# MIRA220CSP-Sheet1.net
KiCad netlist of a schematic drawn in Altium Designer
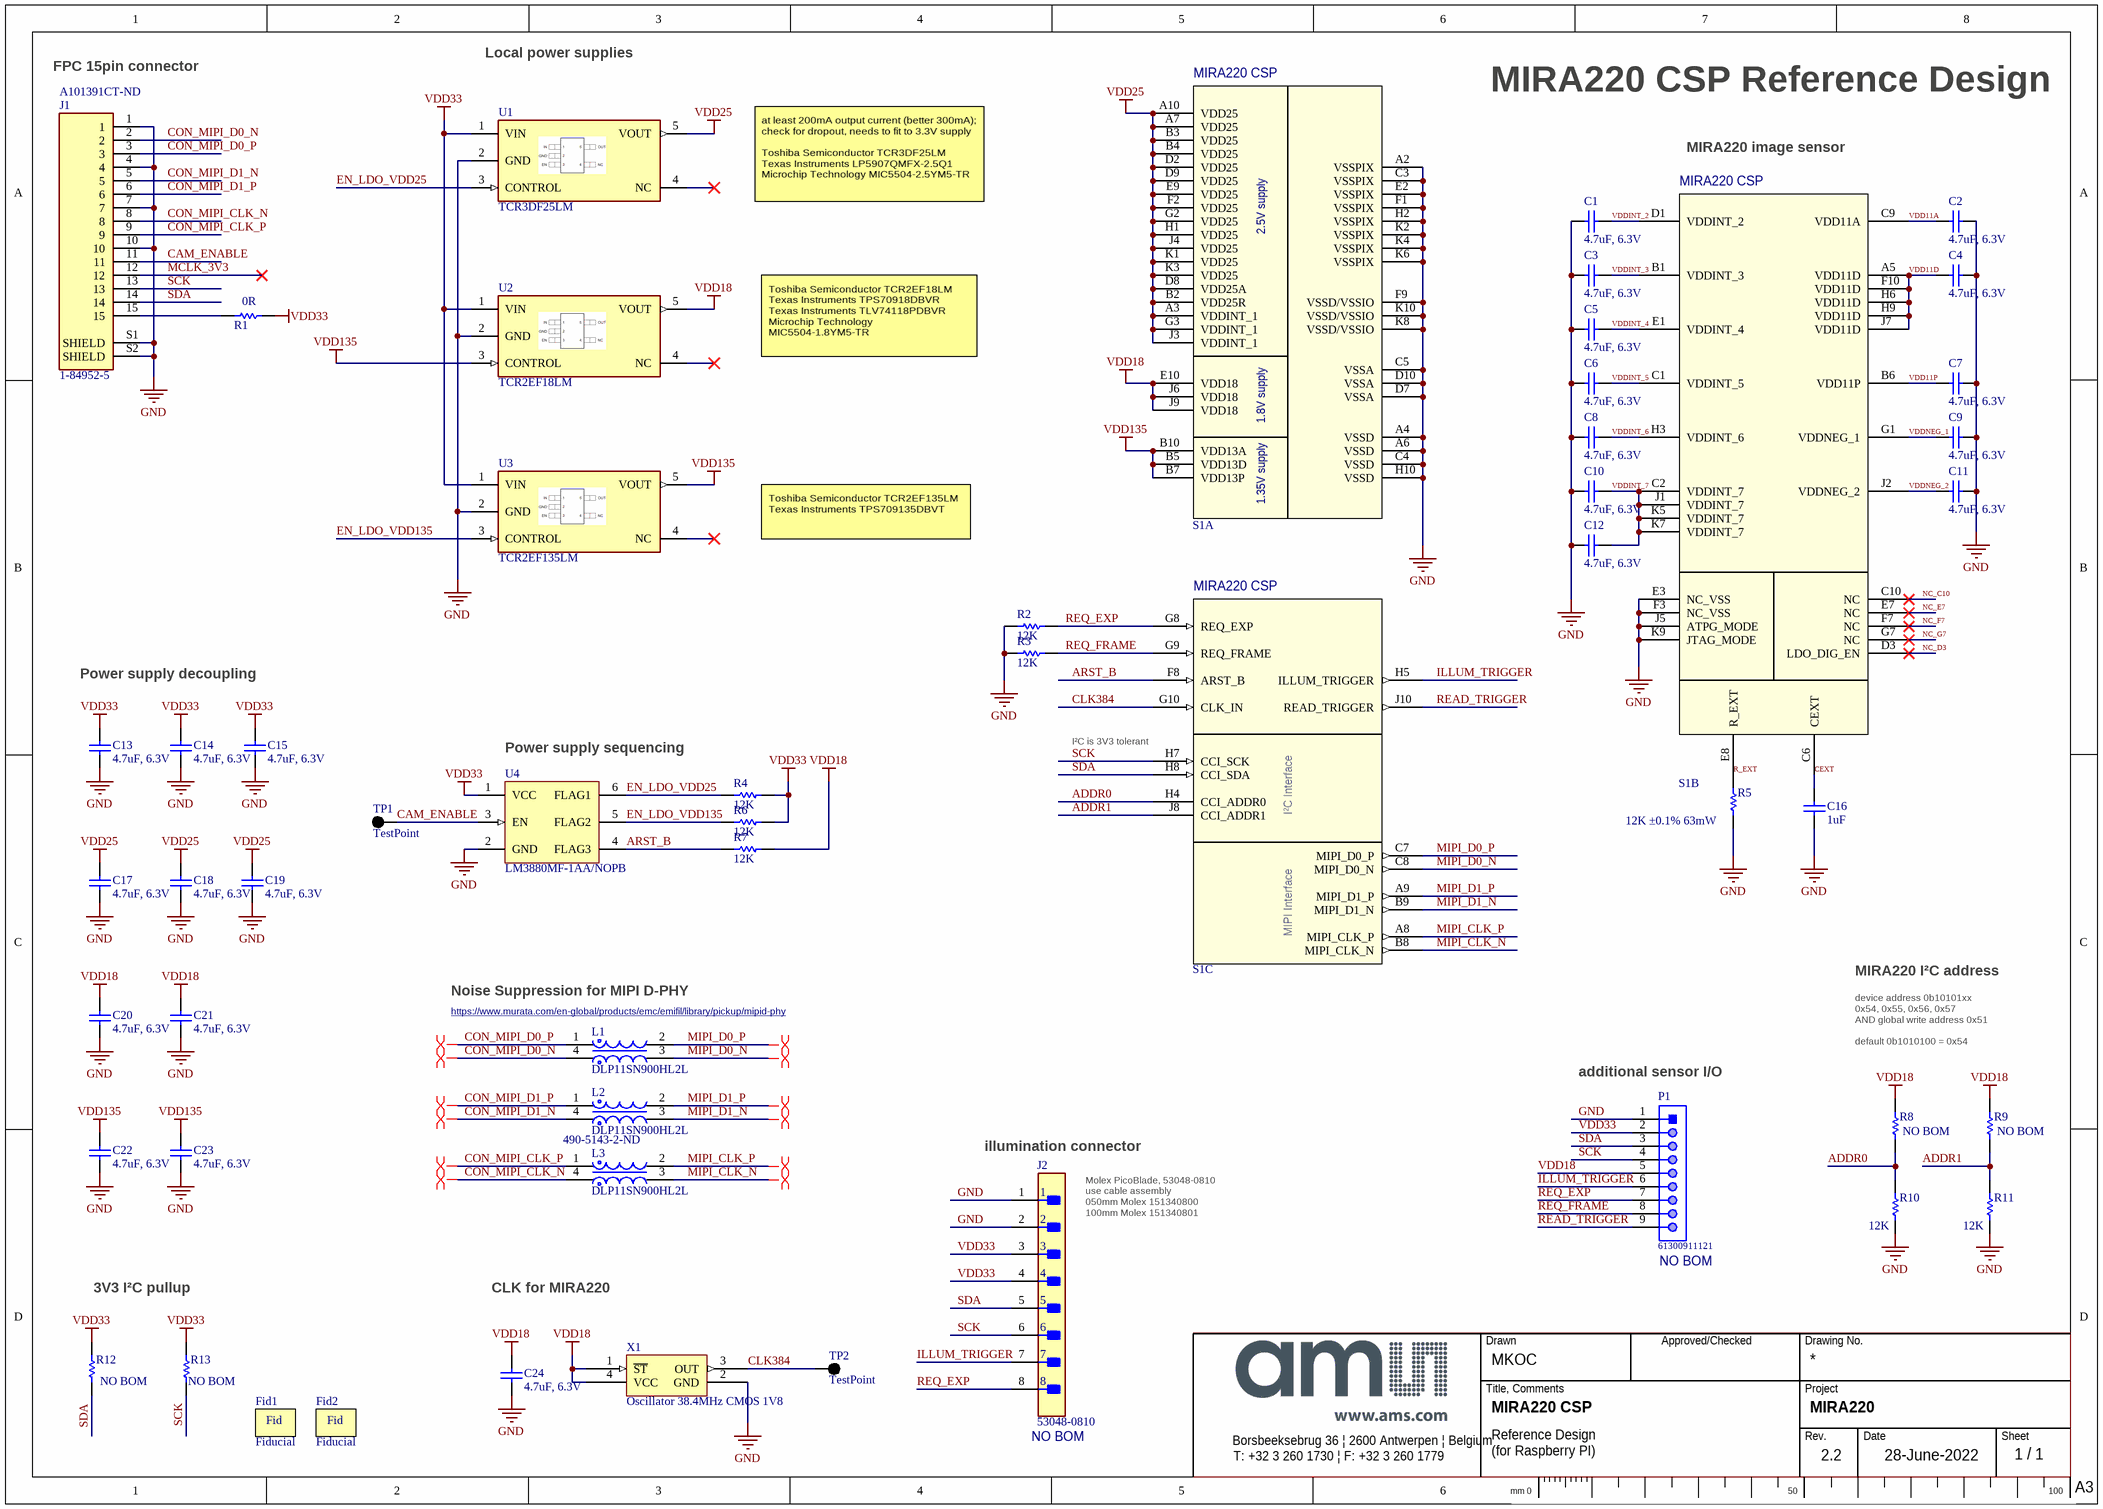
[diagram p0: MIRA220CSP-Sheet1.SchDoc]

(export (version "E")
  (design (tool "Eeschema 10.0.6"))
  (components
    (comp (ref "C1")
      (value "4.7uF, 6.3V")
      (footprint "MIRA220CSP:CAPC0402_N")
      (description "GRM155R60J475ME47D Capacitor 4.7uF, 6.3V, X5R, 0402, ±10% Tolerance,")
      (fields (field (name "TOLERANCE") "±10%") (field (name "PART NUMBER") "GRM155R60J475ME47D"))
      (libsource (lib "altiumlib") (part "cap_unpolarised"))
    )
    (comp (ref "C2")
      (value "4.7uF, 6.3V")
      (footprint "MIRA220CSP:CAPC0402_N")
      (description "GRM155R60J475ME47D Capacitor 4.7uF, 6.3V, X5R, 0402, ±10% Tolerance,")
      (fields (field (name "TOLERANCE") "±10%") (field (name "PART NUMBER") "GRM155R60J475ME47D"))
      (libsource (lib "altiumlib") (part "cap_unpolarised"))
    )
    (comp (ref "C3")
      (value "4.7uF, 6.3V")
      (footprint "MIRA220CSP:CAPC0402_N")
      (description "GRM155R60J475ME47D Capacitor 4.7uF, 6.3V, X5R, 0402, ±10% Tolerance,")
      (fields (field (name "TOLERANCE") "±10%") (field (name "PART NUMBER") "GRM155R60J475ME47D"))
      (libsource (lib "altiumlib") (part "cap_unpolarised"))
    )
    (comp (ref "C4")
      (value "4.7uF, 6.3V")
      (footprint "MIRA220CSP:CAPC0402_N")
      (description "GRM155R60J475ME47D Capacitor 4.7uF, 6.3V, X5R, 0402, ±10% Tolerance,")
      (fields (field (name "TOLERANCE") "±10%") (field (name "PART NUMBER") "GRM155R60J475ME47D"))
      (libsource (lib "altiumlib") (part "cap_unpolarised"))
    )
    (comp (ref "C5")
      (value "4.7uF, 6.3V")
      (footprint "MIRA220CSP:CAPC0402_N")
      (description "GRM155R60J475ME47D Capacitor 4.7uF, 6.3V, X5R, 0402, ±10% Tolerance,")
      (fields (field (name "TOLERANCE") "±10%") (field (name "PART NUMBER") "GRM155R60J475ME47D"))
      (libsource (lib "altiumlib") (part "cap_unpolarised"))
    )
    (comp (ref "C6")
      (value "4.7uF, 6.3V")
      (footprint "MIRA220CSP:CAPC0402_N")
      (description "GRM155R60J475ME47D Capacitor 4.7uF, 6.3V, X5R, 0402, ±10% Tolerance,")
      (fields (field (name "TOLERANCE") "±10%") (field (name "PART NUMBER") "GRM155R60J475ME47D"))
      (libsource (lib "altiumlib") (part "cap_unpolarised"))
    )
    (comp (ref "C7")
      (value "4.7uF, 6.3V")
      (footprint "MIRA220CSP:CAPC0402_N")
      (description "GRM155R60J475ME47D Capacitor 4.7uF, 6.3V, X5R, 0402, ±10% Tolerance,")
      (fields (field (name "TOLERANCE") "±10%") (field (name "PART NUMBER") "GRM155R60J475ME47D"))
      (libsource (lib "altiumlib") (part "cap_unpolarised"))
    )
    (comp (ref "C8")
      (value "4.7uF, 6.3V")
      (footprint "MIRA220CSP:CAPC0402_N")
      (description "GRM155R60J475ME47D Capacitor 4.7uF, 6.3V, X5R, 0402, ±10% Tolerance,")
      (fields (field (name "TOLERANCE") "±10%") (field (name "PART NUMBER") "GRM155R60J475ME47D"))
      (libsource (lib "altiumlib") (part "cap_unpolarised"))
    )
    (comp (ref "C9")
      (value "4.7uF, 6.3V")
      (footprint "MIRA220CSP:CAPC0402_N")
      (description "GRM155R60J475ME47D Capacitor 4.7uF, 6.3V, X5R, 0402, ±10% Tolerance,")
      (fields (field (name "TOLERANCE") "±10%") (field (name "PART NUMBER") "GRM155R60J475ME47D"))
      (libsource (lib "altiumlib") (part "cap_unpolarised"))
    )
    (comp (ref "C10")
      (value "4.7uF, 6.3V")
      (footprint "MIRA220CSP:CAPC0402_N")
      (description "GRM155R60J475ME47D Capacitor 4.7uF, 6.3V, X5R, 0402, ±10% Tolerance,")
      (fields (field (name "TOLERANCE") "±10%") (field (name "PART NUMBER") "GRM155R60J475ME47D"))
      (libsource (lib "altiumlib") (part "cap_unpolarised"))
    )
    (comp (ref "C11")
      (value "4.7uF, 6.3V")
      (footprint "MIRA220CSP:CAPC0402_N")
      (description "GRM155R60J475ME47D Capacitor 4.7uF, 6.3V, X5R, 0402, ±10% Tolerance,")
      (fields (field (name "TOLERANCE") "±10%") (field (name "PART NUMBER") "GRM155R60J475ME47D"))
      (libsource (lib "altiumlib") (part "cap_unpolarised"))
    )
    (comp (ref "C12")
      (value "4.7uF, 6.3V")
      (footprint "MIRA220CSP:CAPC0402_N")
      (description "GRM155R60J475ME47D Capacitor 4.7uF, 6.3V, X5R, 0402, ±10% Tolerance,")
      (fields (field (name "TOLERANCE") "±10%") (field (name "PART NUMBER") "GRM155R60J475ME47D"))
      (libsource (lib "altiumlib") (part "cap_unpolarised"))
    )
    (comp (ref "C13")
      (value "4.7uF, 6.3V")
      (footprint "MIRA220CSP:CAPC0402_N")
      (description "GRM155R60J475ME47D Capacitor 4.7uF, 6.3V, X5R, 0402, ±10% Tolerance,")
      (fields (field (name "TOLERANCE") "±10%") (field (name "PART NUMBER") "GRM155R60J475ME47D"))
      (libsource (lib "altiumlib") (part "cap_unpolarised"))
    )
    (comp (ref "C14")
      (value "4.7uF, 6.3V")
      (footprint "MIRA220CSP:CAPC0402_N")
      (description "GRM155R60J475ME47D Capacitor 4.7uF, 6.3V, X5R, 0402, ±10% Tolerance,")
      (fields (field (name "TOLERANCE") "±10%") (field (name "PART NUMBER") "GRM155R60J475ME47D"))
      (libsource (lib "altiumlib") (part "cap_unpolarised"))
    )
    (comp (ref "C15")
      (value "4.7uF, 6.3V")
      (footprint "MIRA220CSP:CAPC0402_N")
      (description "GRM155R60J475ME47D Capacitor 4.7uF, 6.3V, X5R, 0402, ±10% Tolerance,")
      (fields (field (name "TOLERANCE") "±10%") (field (name "PART NUMBER") "GRM155R60J475ME47D"))
      (libsource (lib "altiumlib") (part "cap_unpolarised"))
    )
    (comp (ref "C16")
      (value "1uF")
      (footprint "MIRA220CSP:CAPC0402_N")
      (description "GRM155R70J105KA12J, Capacitor  0402, ±10% Tolerance, 10V, 1uF")
      (fields (field (name "PART NUMBER") "GRM155R70J105KA12J") (field (name "MANUFACTURER") "Murata"))
      (libsource (lib "altiumlib") (part "cap_unpolarised"))
    )
    (comp (ref "C17")
      (value "4.7uF, 6.3V")
      (footprint "MIRA220CSP:CAPC0402_N")
      (description "GRM155R60J475ME47D Capacitor 4.7uF, 6.3V, X5R, 0402, ±10% Tolerance,")
      (fields (field (name "TOLERANCE") "±10%") (field (name "PART NUMBER") "GRM155R60J475ME47D"))
      (libsource (lib "altiumlib") (part "cap_unpolarised"))
    )
    (comp (ref "C18")
      (value "4.7uF, 6.3V")
      (footprint "MIRA220CSP:CAPC0402_N")
      (description "GRM155R60J475ME47D Capacitor 4.7uF, 6.3V, X5R, 0402, ±10% Tolerance,")
      (fields (field (name "TOLERANCE") "±10%") (field (name "PART NUMBER") "GRM155R60J475ME47D"))
      (libsource (lib "altiumlib") (part "cap_unpolarised"))
    )
    (comp (ref "C19")
      (value "4.7uF, 6.3V")
      (footprint "MIRA220CSP:CAPC0402_N")
      (description "GRM155R60J475ME47D Capacitor 4.7uF, 6.3V, X5R, 0402, ±10% Tolerance,")
      (fields (field (name "TOLERANCE") "±10%") (field (name "PART NUMBER") "GRM155R60J475ME47D"))
      (libsource (lib "altiumlib") (part "cap_unpolarised"))
    )
    (comp (ref "C20")
      (value "4.7uF, 6.3V")
      (footprint "MIRA220CSP:CAPC0402_N")
      (description "GRM155R60J475ME47D Capacitor 4.7uF, 6.3V, X5R, 0402, ±10% Tolerance,")
      (fields (field (name "TOLERANCE") "±10%") (field (name "PART NUMBER") "GRM155R60J475ME47D"))
      (libsource (lib "altiumlib") (part "cap_unpolarised"))
    )
    (comp (ref "C21")
      (value "4.7uF, 6.3V")
      (footprint "MIRA220CSP:CAPC0402_N")
      (description "GRM155R60J475ME47D Capacitor 4.7uF, 6.3V, X5R, 0402, ±10% Tolerance,")
      (fields (field (name "TOLERANCE") "±10%") (field (name "PART NUMBER") "GRM155R60J475ME47D"))
      (libsource (lib "altiumlib") (part "cap_unpolarised"))
    )
    (comp (ref "C22")
      (value "4.7uF, 6.3V")
      (footprint "MIRA220CSP:CAPC0402_N")
      (description "GRM155R60J475ME47D Capacitor 4.7uF, 6.3V, X5R, 0402, ±10% Tolerance,")
      (fields (field (name "TOLERANCE") "±10%") (field (name "PART NUMBER") "GRM155R60J475ME47D"))
      (libsource (lib "altiumlib") (part "cap_unpolarised"))
    )
    (comp (ref "C23")
      (value "4.7uF, 6.3V")
      (footprint "MIRA220CSP:CAPC0402_N")
      (description "GRM155R60J475ME47D Capacitor 4.7uF, 6.3V, X5R, 0402, ±10% Tolerance,")
      (fields (field (name "TOLERANCE") "±10%") (field (name "PART NUMBER") "GRM155R60J475ME47D"))
      (libsource (lib "altiumlib") (part "cap_unpolarised"))
    )
    (comp (ref "C24")
      (value "4.7uF, 6.3V")
      (footprint "MIRA220CSP:CAPC0402_N")
      (description "GRM155R60J475ME47D Capacitor 4.7uF, 6.3V, X5R, 0402, ±10% Tolerance,")
      (fields (field (name "TOLERANCE") "±10%") (field (name "PART NUMBER") "GRM155R60J475ME47D"))
      (libsource (lib "altiumlib") (part "cap_unpolarised"))
    )
    (comp (ref "Fid1")
      (value "Fiducial")
      (footprint "Fiducial")
      (description "Alignment feature for PCB Assembly")
      (fields (field (name "PART NUMBER") "NA"))
      (libsource (lib "altiumlib") (part "Fiducial"))
    )
    (comp (ref "Fid2")
      (value "Fiducial")
      (footprint "Fiducial")
      (description "Alignment feature for PCB Assembly")
      (fields (field (name "PART NUMBER") "NA"))
      (libsource (lib "altiumlib") (part "Fiducial"))
    )
    (comp (ref "J1")
      (value "1-84952-5")
      (footprint "TE_1-84952-5")
      (description "Conn FPC Connector SKT 15 POS 1mm Solder RA SMD T/R")
      (fields (field (name "MF") "TE Connectivity") (field (name "SUPPLIER PART NUMBER 1") "A101391CT-ND"))
      (libsource (lib "MIRA220CSP") (part "1-84952-5"))
    )
    (comp (ref "J2")
      (value "53048-0810")
      (footprint "FP-53048-0810-MFG")
      (description "CONN HEADER R/A 8POS 1.25MM")
      (fields
        (field (name "OCTOPART") "https://octopart.com/53048-0810-molex-276821")
        (field (name "MANUFACTURER") "Molex")
      )
      (libsource (lib "Altium Content Vault") (part "99ec2b232beb5d2356d4d77f6a047f0"))
    )
    (comp (ref "L1")
      (value "DLP11SN900HL2L")
      (footprint "FP-DLP11S-MFG")
      (description "Common Mode Choke, 0504, 90Ω @ 100MHz, 1.88Ω, 20%, 150mA")
      (fields (field (name "TOLERANCE") "20%"))
      (libsource (lib "MIRA220CSP") (part "CMP-2000-06161-2"))
    )
    (comp (ref "L2")
      (value "DLP11SN900HL2L")
      (footprint "FP-DLP11S-MFG")
      (description "Common Mode Choke, 0504, 90Ω @ 100MHz, 1.88Ω, 20%, 150mA")
      (fields (field (name "TOLERANCE") "20%"))
      (libsource (lib "MIRA220CSP") (part "CMP-2000-06161-2"))
    )
    (comp (ref "L3")
      (value "DLP11SN900HL2L")
      (footprint "FP-DLP11S-MFG")
      (description "Common Mode Choke, 0504, 90Ω @ 100MHz, 1.88Ω, 20%, 150mA")
      (fields (field (name "TOLERANCE") "20%") (field (name "SUPPLIER PART NUMBER 1") "490-5143-2-ND"))
      (libsource (lib "MIRA220CSP") (part "CMP-2000-06161-2"))
    )
    (comp (ref "P1")
      (value "61300911121")
      (footprint "61300911121")
      (description "THT Vertical Pin Header WR-PHD, Pitch 2.54 mm, Single Row, 9 pins")
      (fields (field (name "MANUFACTURER") "Wurth Elektronik") (field (name "PUBLISHER") "WurthElektronik"))
      (libsource (lib "Altium Content Vault") (part "WE-CN-1P-M-R9"))
    )
    (comp (ref "R1")
      (value "0R")
      (footprint "MIRA220CSP:RESC0805_N")
      (description "Resistor 0R 0805")
      (fields (field (name "TOLERANCE") "±1%") (field (name "PART NUMBER") "MCWR08X0000FTL"))
      (libsource (lib "altiumlib") (part "Res"))
    )
    (comp (ref "R2")
      (value "12K")
      (footprint "MIRA220CSP:RESC0402_N")
      (description "Resistor 12K 0402, ±0.1% Tolerance, 63mW max Pd, 50V")
      (fields (field (name "TOLERANCE") "±0.1%") (field (name "PART NUMBER") "ERA2AEB123X"))
      (libsource (lib "altiumlib") (part "Res"))
    )
    (comp (ref "R3")
      (value "12K")
      (footprint "MIRA220CSP:RESC0402_N")
      (description "Resistor 12K 0402, ±0.1% Tolerance, 63mW max Pd, 50V")
      (fields (field (name "TOLERANCE") "±0.1%") (field (name "PART NUMBER") "ERA2AEB123X"))
      (libsource (lib "altiumlib") (part "Res"))
    )
    (comp (ref "R4")
      (value "12K")
      (footprint "MIRA220CSP:RESC0402_N")
      (description "Resistor 12K 0402, ±0.1% Tolerance, 63mW max Pd, 50V")
      (fields (field (name "TOLERANCE") "±0.1%") (field (name "PART NUMBER") "ERA2AEB123X"))
      (libsource (lib "altiumlib") (part "Res"))
    )
    (comp (ref "R5")
      (value "12K ±0.1% 63mW")
      (footprint "MIRA220CSP:RESC0402_N")
      (description "Resistor 12K 0402, ±0.1% Tolerance, 63mW max Pd, 50V")
      (fields (field (name "TOLERANCE") "±0.1%") (field (name "PART NUMBER") "ERA2AEB123X"))
      (libsource (lib "altiumlib") (part "Res"))
    )
    (comp (ref "R6")
      (value "12K")
      (footprint "MIRA220CSP:RESC0402_N")
      (description "Resistor 12K 0402, ±0.1% Tolerance, 63mW max Pd, 50V")
      (fields (field (name "TOLERANCE") "±0.1%") (field (name "PART NUMBER") "ERA2AEB123X"))
      (libsource (lib "altiumlib") (part "Res"))
    )
    (comp (ref "R7")
      (value "12K")
      (footprint "MIRA220CSP:RESC0402_N")
      (description "Resistor 12K 0402, ±0.1% Tolerance, 63mW max Pd, 50V")
      (fields (field (name "TOLERANCE") "±0.1%") (field (name "PART NUMBER") "ERA2AEB123X"))
      (libsource (lib "altiumlib") (part "Res"))
    )
    (comp (ref "R8")
      (value "NO BOM")
      (footprint "MIRA220CSP:RESC0402_N")
      (description "Resistor 12K 0402, ±0.1% Tolerance, 63mW max Pd, 50V")
      (fields (field (name "TOLERANCE") "±0.1%") (field (name "PART NUMBER") "ERA2AEB123X"))
      (libsource (lib "altiumlib") (part "Res"))
    )
    (comp (ref "R9")
      (value "NO BOM")
      (footprint "MIRA220CSP:RESC0402_N")
      (description "Resistor 12K 0402, ±0.1% Tolerance, 63mW max Pd, 50V")
      (fields (field (name "TOLERANCE") "±0.1%") (field (name "PART NUMBER") "ERA2AEB123X"))
      (libsource (lib "altiumlib") (part "Res"))
    )
    (comp (ref "R10")
      (value "12K")
      (footprint "MIRA220CSP:RESC0402_N")
      (description "Resistor 12K 0402, ±0.1% Tolerance, 63mW max Pd, 50V")
      (fields (field (name "TOLERANCE") "±0.1%") (field (name "PART NUMBER") "ERA2AEB123X"))
      (libsource (lib "altiumlib") (part "Res"))
    )
    (comp (ref "R11")
      (value "12K")
      (footprint "MIRA220CSP:RESC0402_N")
      (description "Resistor 12K 0402, ±0.1% Tolerance, 63mW max Pd, 50V")
      (fields (field (name "TOLERANCE") "±0.1%") (field (name "PART NUMBER") "ERA2AEB123X"))
      (libsource (lib "altiumlib") (part "Res"))
    )
    (comp (ref "R12")
      (value "NO BOM")
      (footprint "MIRA220CSP:RESC0402_N")
      (description "Resistor 2K 0402, ±0.1% Tolerance, 63mW max Pd, 50V")
      (fields (field (name "TOLERANCE") "±0.1%") (field (name "PART NUMBER") "ERA2AEB123X"))
      (libsource (lib "altiumlib") (part "Res"))
    )
    (comp (ref "R13")
      (value "NO BOM")
      (footprint "MIRA220CSP:RESC0402_N")
      (description "Resistor 2K 0402, ±0.1% Tolerance, 63mW max Pd, 50V")
      (fields (field (name "TOLERANCE") "±0.1%") (field (name "PART NUMBER") "ERA2AEB123X"))
      (libsource (lib "altiumlib") (part "Res"))
    )
    (comp (ref "S1")
      (value "MIRA CSP")
      (footprint "MIRA220CSP")
      (description "Mira220-2QM1WA")
      (libsource (lib "MIRA220CSP") (part "MIRA_CSP"))
    )
    (comp (ref "TP1")
      (value "TestPoint")
      (footprint "MIRA220CSP:TP_075mm")
      (description "Test Point, various footprints")
      (libsource (lib "MIRA220CSP") (part "5001"))
    )
    (comp (ref "TP2")
      (value "TestPoint")
      (footprint "MIRA220CSP:TP_075mm")
      (description "Test Point, various footprints")
      (libsource (lib "MIRA220CSP") (part "5001"))
    )
    (comp (ref "U1")
      (value "TCR3DF25LM")
      (footprint "FP-DBV0005A-IPC_B")
      (description "IC REG LINEAR fixed Voltage, SOT23-5 / SOT-25 / SC74A package")
      (libsource (lib "MIRA220CSP") (part "LDO-STO23-5"))
    )
    (comp (ref "U2")
      (value "TCR2EF18LM")
      (footprint "FP-DBV0005A-IPC_B")
      (description "IC REG LINEAR fixed Voltage, SOT23-5 / SOT-25 / SC74A package")
      (libsource (lib "MIRA220CSP") (part "LDO-STO23-5"))
    )
    (comp (ref "U3")
      (value "TCR2EF135LM")
      (footprint "FP-DBV0005A-IPC_B")
      (description "IC REG LINEAR fixed Voltage, SOT23-5 / SOT-25 / SC74A package")
      (libsource (lib "MIRA220CSP") (part "LDO-STO23-5"))
    )
    (comp (ref "U4")
      (value "LM3880MF-1AA/NOPB")
      (footprint "MIRA220CSP:DBV0006A_N")
      (description "Power Sequencer, 6-pin SOT-23, Pb-Free, 1000 Reel")
      (fields (field (name "MANUFACTURER") "Texas Instruments"))
      (libsource (lib "MIRA220CSP") (part "CMP-0063-01015-4"))
    )
    (comp (ref "X1")
      (value "Oscillator 38.4MHz CMOS 1V8")
      (footprint "2.5x2_OSC")
      (fields
        (field (name "TOLERANCE") "±15ppm")
        (field (name "PART NUMBER") "SG-211SEE38.4000MT3")
        (field (name "MANUFACTURER") "Epson")
      )
      (libsource (lib "altiumlib") (part "SG-211SEE38.4000MT3"))
    )
  )
  (nets
    (net (code "1") (name "/ADDR0") (class "Default")
      (node (ref "R10") (pin "2") (pinfunction "2_2") (pintype "passive"))
      (node (ref "R8") (pin "1") (pinfunction "1_1") (pintype "passive"))
      (node (ref "S1") (pin "H4") (pinfunction "CCI_ADDR0_H4") (pintype "passive"))
    )
    (net (code "2") (name "/ADDR1") (class "Default")
      (node (ref "R11") (pin "2") (pinfunction "2_2") (pintype "passive"))
      (node (ref "R9") (pin "1") (pinfunction "1_1") (pintype "passive"))
      (node (ref "S1") (pin "J8") (pinfunction "CCI_ADDR1_J8") (pintype "passive"))
    )
    (net (code "3") (name "/ARST_B") (class "Default")
      (node (ref "R7") (pin "2") (pinfunction "2_2") (pintype "passive"))
      (node (ref "S1") (pin "F8") (pinfunction "ARST_B_F8") (pintype "input"))
      (node (ref "U4") (pin "4") (pinfunction "FLAG3_4") (pintype "open_collector"))
    )
    (net (code "4") (name "/CAM_ENABLE") (class "Default")
      (node (ref "J1") (pin "11") (pinfunction "11_11") (pintype "passive"))
      (node (ref "TP1") (pin "1") (pintype "passive"))
      (node (ref "U4") (pin "3") (pinfunction "EN_3") (pintype "input"))
    )
    (net (code "5") (name "/CEXT") (class "Default")
      (node (ref "C16") (pin "2") (pinfunction "2_2") (pintype "passive"))
      (node (ref "S1") (pin "C6") (pinfunction "CEXT_C6") (pintype "passive"))
    )
    (net (code "6") (name "/CLK384") (class "Default")
      (node (ref "S1") (pin "G10") (pinfunction "CLK_IN_G10") (pintype "input"))
      (node (ref "TP2") (pin "1") (pintype "passive"))
      (node (ref "X1") (pin "3") (pinfunction "OUT_3") (pintype "output"))
    )
    (net (code "7") (name "/CON_MIPI_CLK_N") (class "Default")
      (node (ref "J1") (pin "8") (pinfunction "8_8") (pintype "passive"))
      (node (ref "L3") (pin "4") (pinfunction "4_4") (pintype "passive"))
    )
    (net (code "8") (name "/CON_MIPI_CLK_P") (class "Default")
      (node (ref "J1") (pin "9") (pinfunction "9_9") (pintype "passive"))
      (node (ref "L3") (pin "1") (pinfunction "1_1") (pintype "passive"))
    )
    (net (code "9") (name "/CON_MIPI_D0_N") (class "Default")
      (node (ref "J1") (pin "2") (pinfunction "2_2") (pintype "passive"))
      (node (ref "L1") (pin "4") (pinfunction "4_4") (pintype "passive"))
    )
    (net (code "10") (name "/CON_MIPI_D0_P") (class "Default")
      (node (ref "J1") (pin "3") (pinfunction "3_3") (pintype "passive"))
      (node (ref "L1") (pin "1") (pinfunction "1_1") (pintype "passive"))
    )
    (net (code "11") (name "/CON_MIPI_D1_N") (class "Default")
      (node (ref "J1") (pin "5") (pinfunction "5_5") (pintype "passive"))
      (node (ref "L2") (pin "4") (pinfunction "4_4") (pintype "passive"))
    )
    (net (code "12") (name "/CON_MIPI_D1_P") (class "Default")
      (node (ref "J1") (pin "6") (pinfunction "6_6") (pintype "passive"))
      (node (ref "L2") (pin "1") (pinfunction "1_1") (pintype "passive"))
    )
    (net (code "13") (name "/EN_LDO_VDD25") (class "Default")
      (node (ref "R4") (pin "2") (pinfunction "2_2") (pintype "passive"))
      (node (ref "U1") (pin "3") (pinfunction "CONTROL_3") (pintype "input"))
      (node (ref "U4") (pin "6") (pinfunction "FLAG1_6") (pintype "open_collector"))
    )
    (net (code "14") (name "/EN_LDO_VDD135") (class "Default")
      (node (ref "R6") (pin "2") (pinfunction "2_2") (pintype "passive"))
      (node (ref "U3") (pin "3") (pinfunction "CONTROL_3") (pintype "input"))
      (node (ref "U4") (pin "5") (pinfunction "FLAG2_5") (pintype "open_collector"))
    )
    (net (code "15") (name "/ILLUM_TRIGGER") (class "Default")
      (node (ref "J2") (pin "7") (pinfunction "7_7") (pintype "passive"))
      (node (ref "P1") (pin "6") (pinfunction "6_6") (pintype "passive"))
      (node (ref "S1") (pin "H5") (pinfunction "ILLUM_TRIGGER_H5") (pintype "output"))
    )
    (net (code "16") (name "/MCLK_3V3") (class "Default")
      (node (ref "J1") (pin "12") (pinfunction "12_12") (pintype "passive+no_connect"))
    )
    (net (code "17") (name "/MIPI_CLK_N") (class "Default")
      (node (ref "L3") (pin "3") (pinfunction "3_3") (pintype "passive"))
      (node (ref "S1") (pin "B8") (pinfunction "MIPI_CLK_N_B8") (pintype "output"))
    )
    (net (code "18") (name "/MIPI_CLK_P") (class "Default")
      (node (ref "L3") (pin "2") (pinfunction "2_2") (pintype "passive"))
      (node (ref "S1") (pin "A8") (pinfunction "MIPI_CLK_P_A8") (pintype "output"))
    )
    (net (code "19") (name "/MIPI_D0_N") (class "Default")
      (node (ref "L1") (pin "3") (pinfunction "3_3") (pintype "passive"))
      (node (ref "S1") (pin "C8") (pinfunction "MIPI_D0_N_C8") (pintype "output"))
    )
    (net (code "20") (name "/MIPI_D0_P") (class "Default")
      (node (ref "L1") (pin "2") (pinfunction "2_2") (pintype "passive"))
      (node (ref "S1") (pin "C7") (pinfunction "MIPI_D0_P_C7") (pintype "output"))
    )
    (net (code "21") (name "/MIPI_D1_N") (class "Default")
      (node (ref "L2") (pin "3") (pinfunction "3_3") (pintype "passive"))
      (node (ref "S1") (pin "B9") (pinfunction "MIPI_D1_N_B9") (pintype "output"))
    )
    (net (code "22") (name "/MIPI_D1_P") (class "Default")
      (node (ref "L2") (pin "2") (pinfunction "2_2") (pintype "passive"))
      (node (ref "S1") (pin "A9") (pinfunction "MIPI_D1_P_A9") (pintype "output"))
    )
    (net (code "23") (name "/NC_C10") (class "Default")
      (node (ref "S1") (pin "C10") (pinfunction "NC_C10") (pintype "passive+no_connect"))
    )
    (net (code "24") (name "/NC_D3") (class "Default")
      (node (ref "S1") (pin "D3") (pinfunction "LDO_DIG_EN_D3") (pintype "passive+no_connect"))
    )
    (net (code "25") (name "/NC_E7") (class "Default")
      (node (ref "S1") (pin "E7") (pinfunction "NC_E7") (pintype "passive+no_connect"))
    )
    (net (code "26") (name "/NC_F7") (class "Default")
      (node (ref "S1") (pin "F7") (pinfunction "NC_F7") (pintype "passive+no_connect"))
    )
    (net (code "27") (name "/NC_G7") (class "Default")
      (node (ref "S1") (pin "G7") (pinfunction "NC_G7") (pintype "passive+no_connect"))
    )
    (net (code "28") (name "/READ_TRIGGER") (class "Default")
      (node (ref "P1") (pin "9") (pinfunction "9_9") (pintype "passive"))
      (node (ref "S1") (pin "J10") (pinfunction "READ_TRIGGER_J10") (pintype "output"))
    )
    (net (code "29") (name "/REQ_EXP") (class "Default")
      (node (ref "J2") (pin "8") (pinfunction "8_8") (pintype "passive"))
      (node (ref "P1") (pin "7") (pinfunction "7_7") (pintype "passive"))
      (node (ref "R2") (pin "1") (pinfunction "1_1") (pintype "passive"))
      (node (ref "S1") (pin "G8") (pinfunction "REQ_EXP_G8") (pintype "input"))
    )
    (net (code "30") (name "/REQ_FRAME") (class "Default")
      (node (ref "P1") (pin "8") (pinfunction "8_8") (pintype "passive"))
      (node (ref "R3") (pin "1") (pinfunction "1_1") (pintype "passive"))
      (node (ref "S1") (pin "G9") (pinfunction "REQ_FRAME_G9") (pintype "input"))
    )
    (net (code "31") (name "/R_EXT") (class "Default")
      (node (ref "R5") (pin "2") (pinfunction "2_2") (pintype "passive"))
      (node (ref "S1") (pin "E8") (pinfunction "R_EXT_E8") (pintype "passive"))
    )
    (net (code "32") (name "/SCK") (class "Default")
      (node (ref "J1") (pin "13") (pinfunction "13_13") (pintype "passive"))
      (node (ref "J2") (pin "6") (pinfunction "6_6") (pintype "passive"))
      (node (ref "P1") (pin "4") (pinfunction "4_4") (pintype "passive"))
      (node (ref "R13") (pin "1") (pinfunction "1_1") (pintype "passive"))
      (node (ref "S1") (pin "H7") (pinfunction "CCI_SCK_H7") (pintype "input"))
    )
    (net (code "33") (name "/SDA") (class "Default")
      (node (ref "J1") (pin "14") (pinfunction "14_14") (pintype "passive"))
      (node (ref "J2") (pin "5") (pinfunction "5_5") (pintype "passive"))
      (node (ref "P1") (pin "3") (pinfunction "3_3") (pintype "passive"))
      (node (ref "R12") (pin "1") (pinfunction "1_1") (pintype "passive"))
      (node (ref "S1") (pin "H8") (pinfunction "CCI_SDA_H8") (pintype "input"))
    )
    (net (code "34") (name "/VDD11A") (class "Default")
      (node (ref "C2") (pin "1") (pinfunction "1_1") (pintype "passive"))
      (node (ref "S1") (pin "C9") (pinfunction "VDD11A_C9") (pintype "passive"))
    )
    (net (code "35") (name "/VDD11D") (class "Default")
      (node (ref "C4") (pin "1") (pinfunction "1_1") (pintype "passive"))
      (node (ref "S1") (pin "A5") (pinfunction "VDD11D_A5") (pintype "passive"))
      (node (ref "S1") (pin "F10") (pinfunction "VDD11D_F10") (pintype "passive"))
      (node (ref "S1") (pin "H6") (pinfunction "VDD11D_H6") (pintype "passive"))
      (node (ref "S1") (pin "H9") (pinfunction "VDD11D_H9") (pintype "passive"))
      (node (ref "S1") (pin "J7") (pinfunction "VDD11D_J7") (pintype "passive"))
    )
    (net (code "36") (name "/VDD11P") (class "Default")
      (node (ref "C7") (pin "1") (pinfunction "1_1") (pintype "passive"))
      (node (ref "S1") (pin "B6") (pinfunction "VDD11P_B6") (pintype "passive"))
    )
    (net (code "37") (name "/VDDINT_2") (class "Default")
      (node (ref "C1") (pin "2") (pinfunction "2_2") (pintype "passive"))
      (node (ref "S1") (pin "D1") (pinfunction "VDDINT_2_D1") (pintype "passive"))
    )
    (net (code "38") (name "/VDDINT_3") (class "Default")
      (node (ref "C3") (pin "2") (pinfunction "2_2") (pintype "passive"))
      (node (ref "S1") (pin "B1") (pinfunction "VDDINT_3_B1") (pintype "passive"))
    )
    (net (code "39") (name "/VDDINT_4") (class "Default")
      (node (ref "C5") (pin "2") (pinfunction "2_2") (pintype "passive"))
      (node (ref "S1") (pin "E1") (pinfunction "VDDINT_4_E1") (pintype "passive"))
    )
    (net (code "40") (name "/VDDINT_5") (class "Default")
      (node (ref "C6") (pin "2") (pinfunction "2_2") (pintype "passive"))
      (node (ref "S1") (pin "C1") (pinfunction "VDDINT_5_C1") (pintype "passive"))
    )
    (net (code "41") (name "/VDDINT_6") (class "Default")
      (node (ref "C8") (pin "2") (pinfunction "2_2") (pintype "passive"))
      (node (ref "S1") (pin "H3") (pinfunction "VDDINT_6_H3") (pintype "passive"))
    )
    (net (code "42") (name "/VDDINT_7") (class "Default")
      (node (ref "C10") (pin "2") (pinfunction "2_2") (pintype "passive"))
      (node (ref "C12") (pin "2") (pinfunction "2_2") (pintype "passive"))
      (node (ref "S1") (pin "C2") (pinfunction "VDDINT_7_C2") (pintype "passive"))
      (node (ref "S1") (pin "J1") (pinfunction "VDDINT_7_J1") (pintype "passive"))
      (node (ref "S1") (pin "K5") (pinfunction "VDDINT_7_K5") (pintype "passive"))
      (node (ref "S1") (pin "K7") (pinfunction "VDDINT_7_K7") (pintype "passive"))
    )
    (net (code "43") (name "/VDDNEG_1") (class "Default")
      (node (ref "C9") (pin "1") (pinfunction "1_1") (pintype "passive"))
      (node (ref "S1") (pin "G1") (pinfunction "VDDNEG_1_G1") (pintype "passive"))
    )
    (net (code "44") (name "/VDDNEG_2") (class "Default")
      (node (ref "C11") (pin "1") (pinfunction "1_1") (pintype "passive"))
      (node (ref "S1") (pin "J2") (pinfunction "VDDNEG_2_J2") (pintype "passive"))
    )
    (net (code "45") (name "GND") (class "Default")
      (node (ref "C1") (pin "1") (pinfunction "1_1") (pintype "passive"))
      (node (ref "C10") (pin "1") (pinfunction "1_1") (pintype "passive"))
      (node (ref "C11") (pin "2") (pinfunction "2_2") (pintype "passive"))
      (node (ref "C12") (pin "1") (pinfunction "1_1") (pintype "passive"))
      (node (ref "C13") (pin "1") (pinfunction "1_1") (pintype "passive"))
      (node (ref "C14") (pin "1") (pinfunction "1_1") (pintype "passive"))
      (node (ref "C15") (pin "1") (pinfunction "1_1") (pintype "passive"))
      (node (ref "C16") (pin "1") (pinfunction "1_1") (pintype "passive"))
      (node (ref "C17") (pin "1") (pinfunction "1_1") (pintype "passive"))
      (node (ref "C18") (pin "1") (pinfunction "1_1") (pintype "passive"))
      (node (ref "C19") (pin "1") (pinfunction "1_1") (pintype "passive"))
      (node (ref "C2") (pin "2") (pinfunction "2_2") (pintype "passive"))
      (node (ref "C20") (pin "1") (pinfunction "1_1") (pintype "passive"))
      (node (ref "C21") (pin "1") (pinfunction "1_1") (pintype "passive"))
      (node (ref "C22") (pin "1") (pinfunction "1_1") (pintype "passive"))
      (node (ref "C23") (pin "1") (pinfunction "1_1") (pintype "passive"))
      (node (ref "C24") (pin "1") (pinfunction "1_1") (pintype "passive"))
      (node (ref "C3") (pin "1") (pinfunction "1_1") (pintype "passive"))
      (node (ref "C4") (pin "2") (pinfunction "2_2") (pintype "passive"))
      (node (ref "C5") (pin "1") (pinfunction "1_1") (pintype "passive"))
      (node (ref "C6") (pin "1") (pinfunction "1_1") (pintype "passive"))
      (node (ref "C7") (pin "2") (pinfunction "2_2") (pintype "passive"))
      (node (ref "C8") (pin "1") (pinfunction "1_1") (pintype "passive"))
      (node (ref "C9") (pin "2") (pinfunction "2_2") (pintype "passive"))
      (node (ref "J1") (pin "1") (pinfunction "1_1") (pintype "passive"))
      (node (ref "J1") (pin "10") (pinfunction "10_10") (pintype "passive"))
      (node (ref "J1") (pin "4") (pinfunction "4_4") (pintype "passive"))
      (node (ref "J1") (pin "7") (pinfunction "7_7") (pintype "passive"))
      (node (ref "J1") (pin "S1") (pinfunction "SHIELD_S1") (pintype "passive"))
      (node (ref "J1") (pin "S2") (pinfunction "SHIELD_S2") (pintype "passive"))
      (node (ref "J2") (pin "1") (pinfunction "1_1") (pintype "passive"))
      (node (ref "J2") (pin "2") (pinfunction "2_2") (pintype "passive"))
      (node (ref "P1") (pin "1") (pinfunction "1_1") (pintype "passive"))
      (node (ref "R10") (pin "1") (pinfunction "1_1") (pintype "passive"))
      (node (ref "R11") (pin "1") (pinfunction "1_1") (pintype "passive"))
      (node (ref "R2") (pin "2") (pinfunction "2_2") (pintype "passive"))
      (node (ref "R3") (pin "2") (pinfunction "2_2") (pintype "passive"))
      (node (ref "R5") (pin "1") (pinfunction "1_1") (pintype "passive"))
      (node (ref "S1") (pin "A2") (pinfunction "VSSPIX_A2") (pintype "power_in"))
      (node (ref "S1") (pin "A4") (pinfunction "VSSD_A4") (pintype "power_in"))
      (node (ref "S1") (pin "A6") (pinfunction "VSSD_A6") (pintype "power_in"))
      (node (ref "S1") (pin "C3") (pinfunction "VSSPIX_C3") (pintype "power_in"))
      (node (ref "S1") (pin "C4") (pinfunction "VSSD_C4") (pintype "power_in"))
      (node (ref "S1") (pin "C5") (pinfunction "VSSA_C5") (pintype "power_in"))
      (node (ref "S1") (pin "D10") (pinfunction "VSSA_D10") (pintype "power_in"))
      (node (ref "S1") (pin "D7") (pinfunction "VSSA_D7") (pintype "power_in"))
      (node (ref "S1") (pin "E2") (pinfunction "VSSPIX_E2") (pintype "power_in"))
      (node (ref "S1") (pin "E3") (pinfunction "NC_VSS_E3") (pintype "passive"))
      (node (ref "S1") (pin "F1") (pinfunction "VSSPIX_F1") (pintype "power_in"))
      (node (ref "S1") (pin "F3") (pinfunction "NC_VSS_F3") (pintype "passive"))
      (node (ref "S1") (pin "F9") (pinfunction "VSSD/VSSIO_F9") (pintype "power_in"))
      (node (ref "S1") (pin "H10") (pinfunction "VSSD_H10") (pintype "power_in"))
      (node (ref "S1") (pin "H2") (pinfunction "VSSPIX_H2") (pintype "power_in"))
      (node (ref "S1") (pin "J5") (pinfunction "ATPG_MODE_J5") (pintype "passive"))
      (node (ref "S1") (pin "K10") (pinfunction "VSSD/VSSIO_K10") (pintype "power_in"))
      (node (ref "S1") (pin "K2") (pinfunction "VSSPIX_K2") (pintype "power_in"))
      (node (ref "S1") (pin "K4") (pinfunction "VSSPIX_K4") (pintype "power_in"))
      (node (ref "S1") (pin "K6") (pinfunction "VSSPIX_K6") (pintype "power_in"))
      (node (ref "S1") (pin "K8") (pinfunction "VSSD/VSSIO_K8") (pintype "power_in"))
      (node (ref "S1") (pin "K9") (pinfunction "JTAG_MODE_K9") (pintype "passive"))
      (node (ref "U1") (pin "2") (pinfunction "GND_2") (pintype "power_in"))
      (node (ref "U2") (pin "2") (pinfunction "GND_2") (pintype "power_in"))
      (node (ref "U3") (pin "2") (pinfunction "GND_2") (pintype "power_in"))
      (node (ref "U4") (pin "2") (pinfunction "GND_2") (pintype "power_in"))
      (node (ref "X1") (pin "2") (pinfunction "GND_2") (pintype "power_in"))
    )
    (net (code "46") (name "Net-(J1-Pad15)") (class "Default")
      (node (ref "J1") (pin "15") (pinfunction "15_15") (pintype "passive"))
      (node (ref "R1") (pin "1") (pinfunction "1_1") (pintype "passive"))
    )
    (net (code "47") (name "VDD18") (class "Default")
      (node (ref "C20") (pin "2") (pinfunction "2_2") (pintype "passive"))
      (node (ref "C21") (pin "2") (pinfunction "2_2") (pintype "passive"))
      (node (ref "C24") (pin "2") (pinfunction "2_2") (pintype "passive"))
      (node (ref "P1") (pin "5") (pinfunction "5_5") (pintype "passive"))
      (node (ref "R7") (pin "1") (pinfunction "1_1") (pintype "passive"))
      (node (ref "R8") (pin "2") (pinfunction "2_2") (pintype "passive"))
      (node (ref "R9") (pin "2") (pinfunction "2_2") (pintype "passive"))
      (node (ref "S1") (pin "E10") (pinfunction "VDD18_E10") (pintype "power_in"))
      (node (ref "S1") (pin "J6") (pinfunction "VDD18_J6") (pintype "power_in"))
      (node (ref "S1") (pin "J9") (pinfunction "VDD18_J9") (pintype "power_in"))
      (node (ref "U2") (pin "5") (pinfunction "VOUT_5") (pintype "output"))
      (node (ref "X1") (pin "1") (pinfunction "~{ST}_1") (pintype "input"))
      (node (ref "X1") (pin "4") (pinfunction "VCC_4") (pintype "power_in"))
    )
    (net (code "48") (name "VDD25") (class "Default")
      (node (ref "C17") (pin "2") (pinfunction "2_2") (pintype "passive"))
      (node (ref "C18") (pin "2") (pinfunction "2_2") (pintype "passive"))
      (node (ref "C19") (pin "2") (pinfunction "2_2") (pintype "passive"))
      (node (ref "S1") (pin "A10") (pinfunction "VDD25_A10") (pintype "power_in"))
      (node (ref "S1") (pin "A3") (pinfunction "VDDINT_1_A3") (pintype "power_in"))
      (node (ref "S1") (pin "A7") (pinfunction "VDD25_A7") (pintype "power_in"))
      (node (ref "S1") (pin "B2") (pinfunction "VDD25R_B2") (pintype "power_in"))
      (node (ref "S1") (pin "B3") (pinfunction "VDD25_B3") (pintype "power_in"))
      (node (ref "S1") (pin "B4") (pinfunction "VDD25_B4") (pintype "power_in"))
      (node (ref "S1") (pin "D2") (pinfunction "VDD25_D2") (pintype "power_in"))
      (node (ref "S1") (pin "D8") (pinfunction "VDD25A_D8") (pintype "power_in"))
      (node (ref "S1") (pin "D9") (pinfunction "VDD25_D9") (pintype "power_in"))
      (node (ref "S1") (pin "E9") (pinfunction "VDD25_E9") (pintype "power_in"))
      (node (ref "S1") (pin "F2") (pinfunction "VDD25_F2") (pintype "power_in"))
      (node (ref "S1") (pin "G2") (pinfunction "VDD25_G2") (pintype "power_in"))
      (node (ref "S1") (pin "G3") (pinfunction "VDDINT_1_G3") (pintype "power_in"))
      (node (ref "S1") (pin "H1") (pinfunction "VDD25_H1") (pintype "power_in"))
      (node (ref "S1") (pin "J3") (pinfunction "VDDINT_1_J3") (pintype "power_in"))
      (node (ref "S1") (pin "J4") (pinfunction "VDD25_J4") (pintype "power_in"))
      (node (ref "S1") (pin "K1") (pinfunction "VDD25_K1") (pintype "power_in"))
      (node (ref "S1") (pin "K3") (pinfunction "VDD25_K3") (pintype "power_in"))
      (node (ref "U1") (pin "5") (pinfunction "VOUT_5") (pintype "output"))
    )
    (net (code "49") (name "VDD33") (class "Default")
      (node (ref "C13") (pin "2") (pinfunction "2_2") (pintype "passive"))
      (node (ref "C14") (pin "2") (pinfunction "2_2") (pintype "passive"))
      (node (ref "C15") (pin "2") (pinfunction "2_2") (pintype "passive"))
      (node (ref "J2") (pin "3") (pinfunction "3_3") (pintype "passive"))
      (node (ref "J2") (pin "4") (pinfunction "4_4") (pintype "passive"))
      (node (ref "P1") (pin "2") (pinfunction "2_2") (pintype "passive"))
      (node (ref "R1") (pin "2") (pinfunction "2_2") (pintype "passive"))
      (node (ref "R12") (pin "2") (pinfunction "2_2") (pintype "passive"))
      (node (ref "R13") (pin "2") (pinfunction "2_2") (pintype "passive"))
      (node (ref "R4") (pin "1") (pinfunction "1_1") (pintype "passive"))
      (node (ref "R6") (pin "1") (pinfunction "1_1") (pintype "passive"))
      (node (ref "U1") (pin "1") (pinfunction "VIN_1") (pintype "power_in"))
      (node (ref "U2") (pin "1") (pinfunction "VIN_1") (pintype "power_in"))
      (node (ref "U3") (pin "1") (pinfunction "VIN_1") (pintype "power_in"))
      (node (ref "U4") (pin "1") (pinfunction "VCC_1") (pintype "power_in"))
    )
    (net (code "50") (name "VDD135") (class "Default")
      (node (ref "C22") (pin "2") (pinfunction "2_2") (pintype "passive"))
      (node (ref "C23") (pin "2") (pinfunction "2_2") (pintype "passive"))
      (node (ref "S1") (pin "B10") (pinfunction "VDD13A_B10") (pintype "power_in"))
      (node (ref "S1") (pin "B5") (pinfunction "VDD13D_B5") (pintype "power_in"))
      (node (ref "S1") (pin "B7") (pinfunction "VDD13P_B7") (pintype "power_in"))
      (node (ref "U2") (pin "3") (pinfunction "CONTROL_3") (pintype "input"))
      (node (ref "U3") (pin "5") (pinfunction "VOUT_5") (pintype "output"))
    )
    (net (code "51") (name "unconnected-(U1-NC-Pad4)") (class "Default")
      (node (ref "U1") (pin "4") (pinfunction "NC_4") (pintype "passive+no_connect"))
    )
    (net (code "52") (name "unconnected-(U2-NC-Pad4)") (class "Default")
      (node (ref "U2") (pin "4") (pinfunction "NC_4") (pintype "passive+no_connect"))
    )
    (net (code "53") (name "unconnected-(U3-NC-Pad4)") (class "Default")
      (node (ref "U3") (pin "4") (pinfunction "NC_4") (pintype "passive+no_connect"))
    )
  )
)
